# 10_Speed.net
KiCad netlist of a schematic drawn in Altium Designer
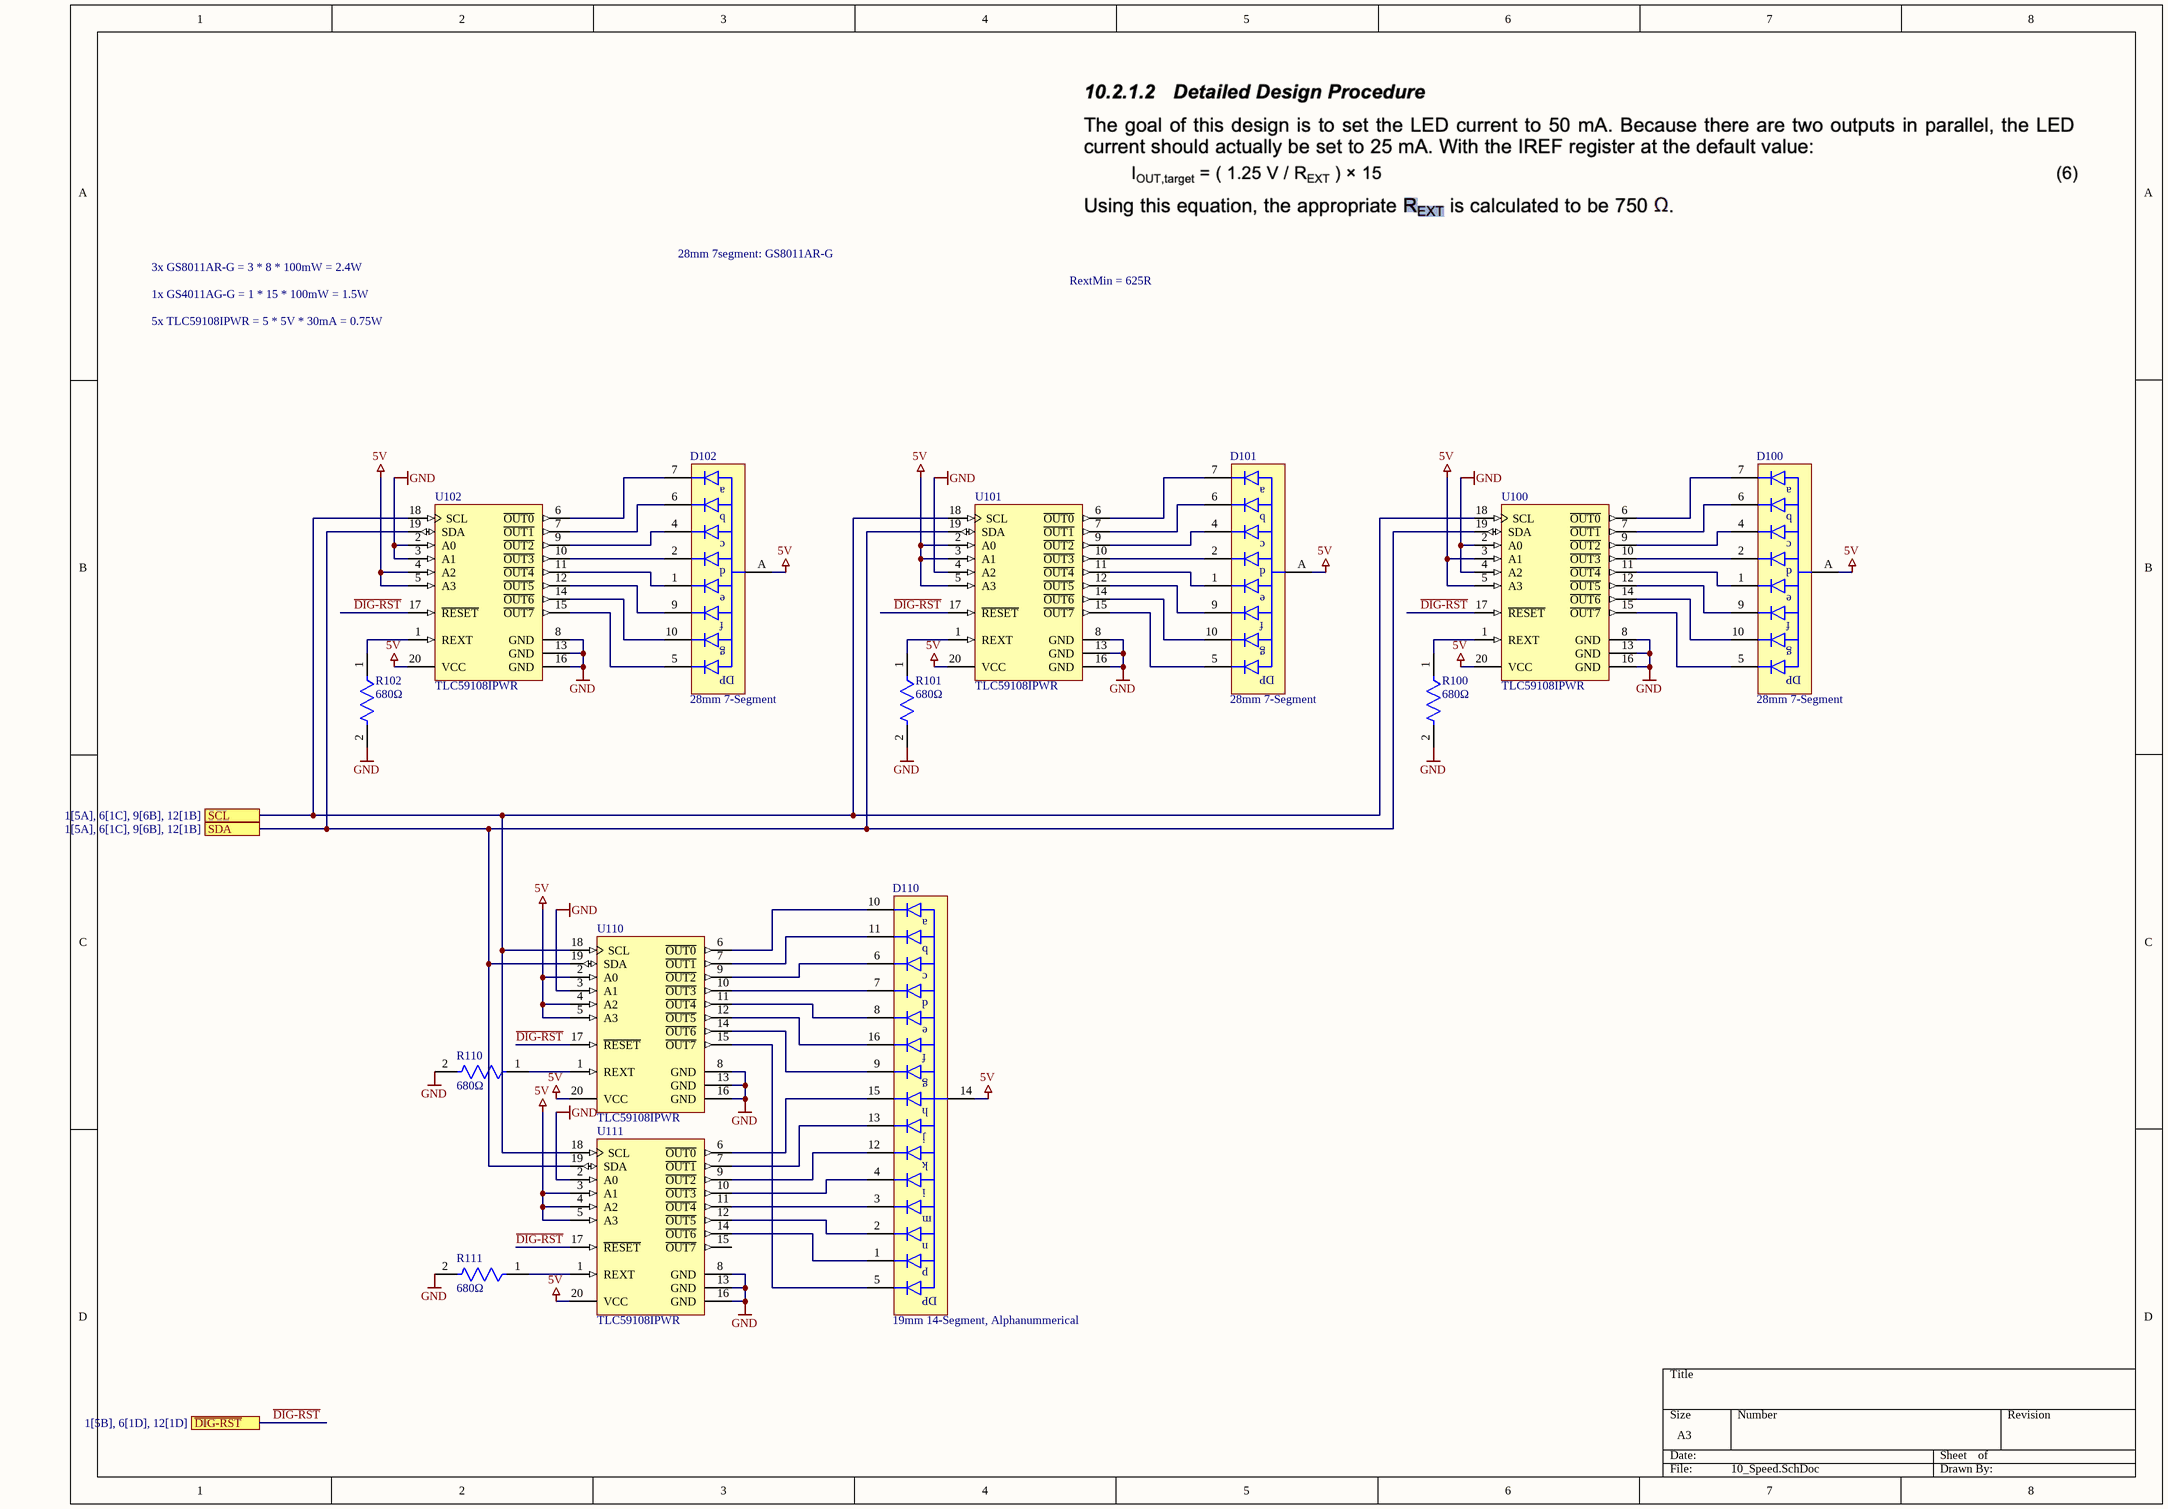
[diagram p0: 10_Speed.SchDoc]

(export (version "E")
  (design (tool "Eeschema 10.0.6"))
  (components
    (comp (ref "D100")
      (value "28mm 7-Segment")
      (footprint "GS8011AR-G")
      (description "SMD, 28x16.8mm 7-Segment")
      (libsource (lib "AltiumLib_MILUTIN") (part "GS8011AR-G"))
    )
    (comp (ref "D101")
      (value "28mm 7-Segment")
      (footprint "GS8011AR-G")
      (description "SMD, 28x16.8mm 7-Segment")
      (libsource (lib "AltiumLib_MILUTIN") (part "GS8011AR-G"))
    )
    (comp (ref "D102")
      (value "28mm 7-Segment")
      (footprint "GS8011AR-G")
      (description "SMD, 28x16.8mm 7-Segment")
      (libsource (lib "AltiumLib_MILUTIN") (part "GS8011AR-G"))
    )
    (comp (ref "D110")
      (value "19mm 14-Segment, Alphanummerical")
      (footprint "GS4011AG-G")
      (description "SMD, 19x9.3mm 14-Segment, Alphanummerical")
      (libsource (lib "AltiumLib_MILUTIN") (part "GS4011AG-G"))
    )
    (comp (ref "R100")
      (value "680Ω")
      (footprint "FP-CRCW0603-e3-IPC_A")
      (description "RES Thick Film, 680Ω, 5%, 0.1W, 200ppm/°C, 0603\r\nCRCW0603680RJNEA")
      (fields (field (name "TOLERANCE") "5%"))
      (libsource (lib "Altium Content Vault") (part "1029c3af85768c4190bb7ad29bc67b5"))
    )
    (comp (ref "R101")
      (value "680Ω")
      (footprint "FP-CRCW0603-e3-IPC_A")
      (description "RES Thick Film, 680Ω, 5%, 0.1W, 200ppm/°C, 0603\r\nCRCW0603680RJNEA")
      (fields (field (name "TOLERANCE") "5%"))
      (libsource (lib "Altium Content Vault") (part "1029c3af85768c4190bb7ad29bc67b5"))
    )
    (comp (ref "R102")
      (value "680Ω")
      (footprint "FP-CRCW0603-e3-IPC_A")
      (description "RES Thick Film, 680Ω, 5%, 0.1W, 200ppm/°C, 0603\r\nCRCW0603680RJNEA")
      (fields (field (name "TOLERANCE") "5%"))
      (libsource (lib "Altium Content Vault") (part "1029c3af85768c4190bb7ad29bc67b5"))
    )
    (comp (ref "R110")
      (value "680Ω")
      (footprint "FP-CRCW0603-e3-IPC_A")
      (description "RES Thick Film, 680Ω, 5%, 0.1W, 200ppm/°C, 0603\r\nCRCW0603680RJNEA")
      (fields (field (name "TOLERANCE") "5%"))
      (libsource (lib "Altium Content Vault") (part "1029c3af85768c4190bb7ad29bc67b5"))
    )
    (comp (ref "R111")
      (value "680Ω")
      (footprint "FP-CRCW0603-e3-IPC_A")
      (description "RES Thick Film, 680Ω, 5%, 0.1W, 200ppm/°C, 0603\r\nCRCW0603680RJNEA")
      (fields (field (name "TOLERANCE") "5%"))
      (libsource (lib "Altium Content Vault") (part "1029c3af85768c4190bb7ad29bc67b5"))
    )
    (comp (ref "U100")
      (value "TLC59108IPWR")
      (footprint "PW0020A_M")
      (fields (field (name "MANUFACTURER") "Texas Instruments"))
      (libsource (lib "Altium Content Vault") (part "TI-TLC59108PW20"))
    )
    (comp (ref "U101")
      (value "TLC59108IPWR")
      (footprint "PW0020A_M")
      (fields (field (name "MANUFACTURER") "Texas Instruments"))
      (libsource (lib "Altium Content Vault") (part "TI-TLC59108PW20"))
    )
    (comp (ref "U102")
      (value "TLC59108IPWR")
      (footprint "PW0020A_M")
      (fields (field (name "MANUFACTURER") "Texas Instruments"))
      (libsource (lib "Altium Content Vault") (part "TI-TLC59108PW20"))
    )
    (comp (ref "U110")
      (value "TLC59108IPWR")
      (footprint "PW0020A_M")
      (fields (field (name "MANUFACTURER") "Texas Instruments"))
      (libsource (lib "Altium Content Vault") (part "TI-TLC59108PW20"))
    )
    (comp (ref "U111")
      (value "TLC59108IPWR")
      (footprint "PW0020A_M")
      (fields (field (name "MANUFACTURER") "Texas Instruments"))
      (libsource (lib "Altium Content Vault") (part "TI-TLC59108PW20"))
    )
  )
  (nets
    (net (code "1") (name "/SCL") (class "Default")
      (node (ref "U100") (pin "18") (pinfunction "SCL_18") (pintype "input"))
      (node (ref "U101") (pin "18") (pinfunction "SCL_18") (pintype "input"))
      (node (ref "U102") (pin "18") (pinfunction "SCL_18") (pintype "input"))
      (node (ref "U110") (pin "18") (pinfunction "SCL_18") (pintype "input"))
      (node (ref "U111") (pin "18") (pinfunction "SCL_18") (pintype "input"))
    )
    (net (code "2") (name "/SDA") (class "Default")
      (node (ref "U100") (pin "19") (pinfunction "SDA_19") (pintype "bidirectional"))
      (node (ref "U101") (pin "19") (pinfunction "SDA_19") (pintype "bidirectional"))
      (node (ref "U102") (pin "19") (pinfunction "SDA_19") (pintype "bidirectional"))
      (node (ref "U110") (pin "19") (pinfunction "SDA_19") (pintype "bidirectional"))
      (node (ref "U111") (pin "19") (pinfunction "SDA_19") (pintype "bidirectional"))
    )
    (net (code "3") (name "/~{DIG-RST}") (class "Default")
      (node (ref "U100") (pin "17") (pinfunction "~{RESET}_17") (pintype "input"))
      (node (ref "U101") (pin "17") (pinfunction "~{RESET}_17") (pintype "input"))
      (node (ref "U102") (pin "17") (pinfunction "~{RESET}_17") (pintype "input"))
      (node (ref "U110") (pin "17") (pinfunction "~{RESET}_17") (pintype "input"))
      (node (ref "U111") (pin "17") (pinfunction "~{RESET}_17") (pintype "input"))
    )
    (net (code "4") (name "5V") (class "Default")
      (node (ref "D100") (pin "A") (pinfunction "A_A") (pintype "passive"))
      (node (ref "D101") (pin "A") (pinfunction "A_A") (pintype "passive"))
      (node (ref "D102") (pin "A") (pinfunction "A_A") (pintype "passive"))
      (node (ref "D110") (pin "14") (pinfunction "14_14") (pintype "passive"))
      (node (ref "U100") (pin "20") (pinfunction "VCC_20") (pintype "power_in"))
      (node (ref "U100") (pin "3") (pinfunction "A1_3") (pintype "input"))
      (node (ref "U100") (pin "5") (pinfunction "A3_5") (pintype "input"))
      (node (ref "U101") (pin "2") (pinfunction "A0_2") (pintype "input"))
      (node (ref "U101") (pin "20") (pinfunction "VCC_20") (pintype "power_in"))
      (node (ref "U101") (pin "3") (pinfunction "A1_3") (pintype "input"))
      (node (ref "U101") (pin "5") (pinfunction "A3_5") (pintype "input"))
      (node (ref "U102") (pin "20") (pinfunction "VCC_20") (pintype "power_in"))
      (node (ref "U102") (pin "4") (pinfunction "A2_4") (pintype "input"))
      (node (ref "U102") (pin "5") (pinfunction "A3_5") (pintype "input"))
      (node (ref "U110") (pin "2") (pinfunction "A0_2") (pintype "input"))
      (node (ref "U110") (pin "20") (pinfunction "VCC_20") (pintype "power_in"))
      (node (ref "U110") (pin "4") (pinfunction "A2_4") (pintype "input"))
      (node (ref "U110") (pin "5") (pinfunction "A3_5") (pintype "input"))
      (node (ref "U111") (pin "20") (pinfunction "VCC_20") (pintype "power_in"))
      (node (ref "U111") (pin "3") (pinfunction "A1_3") (pintype "input"))
      (node (ref "U111") (pin "4") (pinfunction "A2_4") (pintype "input"))
      (node (ref "U111") (pin "5") (pinfunction "A3_5") (pintype "input"))
    )
    (net (code "5") (name "GND") (class "Default")
      (node (ref "R100") (pin "2") (pinfunction "2_2") (pintype "passive"))
      (node (ref "R101") (pin "2") (pinfunction "2_2") (pintype "passive"))
      (node (ref "R102") (pin "2") (pinfunction "2_2") (pintype "passive"))
      (node (ref "R110") (pin "2") (pinfunction "2_2") (pintype "passive"))
      (node (ref "R111") (pin "2") (pinfunction "2_2") (pintype "passive"))
      (node (ref "U100") (pin "13") (pinfunction "GND_13") (pintype "power_in"))
      (node (ref "U100") (pin "16") (pinfunction "GND_16") (pintype "power_in"))
      (node (ref "U100") (pin "2") (pinfunction "A0_2") (pintype "input"))
      (node (ref "U100") (pin "4") (pinfunction "A2_4") (pintype "input"))
      (node (ref "U100") (pin "8") (pinfunction "GND_8") (pintype "power_in"))
      (node (ref "U101") (pin "13") (pinfunction "GND_13") (pintype "power_in"))
      (node (ref "U101") (pin "16") (pinfunction "GND_16") (pintype "power_in"))
      (node (ref "U101") (pin "4") (pinfunction "A2_4") (pintype "input"))
      (node (ref "U101") (pin "8") (pinfunction "GND_8") (pintype "power_in"))
      (node (ref "U102") (pin "13") (pinfunction "GND_13") (pintype "power_in"))
      (node (ref "U102") (pin "16") (pinfunction "GND_16") (pintype "power_in"))
      (node (ref "U102") (pin "2") (pinfunction "A0_2") (pintype "input"))
      (node (ref "U102") (pin "3") (pinfunction "A1_3") (pintype "input"))
      (node (ref "U102") (pin "8") (pinfunction "GND_8") (pintype "power_in"))
      (node (ref "U110") (pin "13") (pinfunction "GND_13") (pintype "power_in"))
      (node (ref "U110") (pin "16") (pinfunction "GND_16") (pintype "power_in"))
      (node (ref "U110") (pin "3") (pinfunction "A1_3") (pintype "input"))
      (node (ref "U110") (pin "8") (pinfunction "GND_8") (pintype "power_in"))
      (node (ref "U111") (pin "13") (pinfunction "GND_13") (pintype "power_in"))
      (node (ref "U111") (pin "16") (pinfunction "GND_16") (pintype "power_in"))
      (node (ref "U111") (pin "2") (pinfunction "A0_2") (pintype "input"))
      (node (ref "U111") (pin "8") (pinfunction "GND_8") (pintype "power_in"))
    )
    (net (code "6") (name "Net-(U100-REXT)") (class "Default")
      (node (ref "R100") (pin "1") (pinfunction "1_1") (pintype "passive"))
      (node (ref "U100") (pin "1") (pinfunction "REXT_1") (pintype "input"))
    )
    (net (code "7") (name "Net-(U100-~{OUT0})") (class "Default")
      (node (ref "D100") (pin "7") (pinfunction "7_7") (pintype "passive"))
      (node (ref "U100") (pin "6") (pinfunction "~{OUT0}_6") (pintype "output"))
    )
    (net (code "8") (name "Net-(U100-~{OUT1})") (class "Default")
      (node (ref "D100") (pin "6") (pinfunction "6_6") (pintype "passive"))
      (node (ref "U100") (pin "7") (pinfunction "~{OUT1}_7") (pintype "output"))
    )
    (net (code "9") (name "Net-(U100-~{OUT2})") (class "Default")
      (node (ref "D100") (pin "4") (pinfunction "4_4") (pintype "passive"))
      (node (ref "U100") (pin "9") (pinfunction "~{OUT2}_9") (pintype "output"))
    )
    (net (code "10") (name "Net-(U100-~{OUT3})") (class "Default")
      (node (ref "D100") (pin "2") (pinfunction "2_2") (pintype "passive"))
      (node (ref "U100") (pin "10") (pinfunction "~{OUT3}_10") (pintype "output"))
    )
    (net (code "11") (name "Net-(U100-~{OUT4})") (class "Default")
      (node (ref "D100") (pin "1") (pinfunction "1_1") (pintype "passive"))
      (node (ref "U100") (pin "11") (pinfunction "~{OUT4}_11") (pintype "output"))
    )
    (net (code "12") (name "Net-(U100-~{OUT5})") (class "Default")
      (node (ref "D100") (pin "9") (pinfunction "9_9") (pintype "passive"))
      (node (ref "U100") (pin "12") (pinfunction "~{OUT5}_12") (pintype "output"))
    )
    (net (code "13") (name "Net-(U100-~{OUT6})") (class "Default")
      (node (ref "D100") (pin "10") (pinfunction "10_10") (pintype "passive"))
      (node (ref "U100") (pin "14") (pinfunction "~{OUT6}_14") (pintype "output"))
    )
    (net (code "14") (name "Net-(U100-~{OUT7})") (class "Default")
      (node (ref "D100") (pin "5") (pinfunction "5_5") (pintype "passive"))
      (node (ref "U100") (pin "15") (pinfunction "~{OUT7}_15") (pintype "output"))
    )
    (net (code "15") (name "Net-(U101-REXT)") (class "Default")
      (node (ref "R101") (pin "1") (pinfunction "1_1") (pintype "passive"))
      (node (ref "U101") (pin "1") (pinfunction "REXT_1") (pintype "input"))
    )
    (net (code "16") (name "Net-(U101-~{OUT0})") (class "Default")
      (node (ref "D101") (pin "7") (pinfunction "7_7") (pintype "passive"))
      (node (ref "U101") (pin "6") (pinfunction "~{OUT0}_6") (pintype "output"))
    )
    (net (code "17") (name "Net-(U101-~{OUT1})") (class "Default")
      (node (ref "D101") (pin "6") (pinfunction "6_6") (pintype "passive"))
      (node (ref "U101") (pin "7") (pinfunction "~{OUT1}_7") (pintype "output"))
    )
    (net (code "18") (name "Net-(U101-~{OUT2})") (class "Default")
      (node (ref "D101") (pin "4") (pinfunction "4_4") (pintype "passive"))
      (node (ref "U101") (pin "9") (pinfunction "~{OUT2}_9") (pintype "output"))
    )
    (net (code "19") (name "Net-(U101-~{OUT3})") (class "Default")
      (node (ref "D101") (pin "2") (pinfunction "2_2") (pintype "passive"))
      (node (ref "U101") (pin "10") (pinfunction "~{OUT3}_10") (pintype "output"))
    )
    (net (code "20") (name "Net-(U101-~{OUT4})") (class "Default")
      (node (ref "D101") (pin "1") (pinfunction "1_1") (pintype "passive"))
      (node (ref "U101") (pin "11") (pinfunction "~{OUT4}_11") (pintype "output"))
    )
    (net (code "21") (name "Net-(U101-~{OUT5})") (class "Default")
      (node (ref "D101") (pin "9") (pinfunction "9_9") (pintype "passive"))
      (node (ref "U101") (pin "12") (pinfunction "~{OUT5}_12") (pintype "output"))
    )
    (net (code "22") (name "Net-(U101-~{OUT6})") (class "Default")
      (node (ref "D101") (pin "10") (pinfunction "10_10") (pintype "passive"))
      (node (ref "U101") (pin "14") (pinfunction "~{OUT6}_14") (pintype "output"))
    )
    (net (code "23") (name "Net-(U101-~{OUT7})") (class "Default")
      (node (ref "D101") (pin "5") (pinfunction "5_5") (pintype "passive"))
      (node (ref "U101") (pin "15") (pinfunction "~{OUT7}_15") (pintype "output"))
    )
    (net (code "24") (name "Net-(U102-REXT)") (class "Default")
      (node (ref "R102") (pin "1") (pinfunction "1_1") (pintype "passive"))
      (node (ref "U102") (pin "1") (pinfunction "REXT_1") (pintype "input"))
    )
    (net (code "25") (name "Net-(U102-~{OUT0})") (class "Default")
      (node (ref "D102") (pin "7") (pinfunction "7_7") (pintype "passive"))
      (node (ref "U102") (pin "6") (pinfunction "~{OUT0}_6") (pintype "output"))
    )
    (net (code "26") (name "Net-(U102-~{OUT1})") (class "Default")
      (node (ref "D102") (pin "6") (pinfunction "6_6") (pintype "passive"))
      (node (ref "U102") (pin "7") (pinfunction "~{OUT1}_7") (pintype "output"))
    )
    (net (code "27") (name "Net-(U102-~{OUT2})") (class "Default")
      (node (ref "D102") (pin "4") (pinfunction "4_4") (pintype "passive"))
      (node (ref "U102") (pin "9") (pinfunction "~{OUT2}_9") (pintype "output"))
    )
    (net (code "28") (name "Net-(U102-~{OUT3})") (class "Default")
      (node (ref "D102") (pin "2") (pinfunction "2_2") (pintype "passive"))
      (node (ref "U102") (pin "10") (pinfunction "~{OUT3}_10") (pintype "output"))
    )
    (net (code "29") (name "Net-(U102-~{OUT4})") (class "Default")
      (node (ref "D102") (pin "1") (pinfunction "1_1") (pintype "passive"))
      (node (ref "U102") (pin "11") (pinfunction "~{OUT4}_11") (pintype "output"))
    )
    (net (code "30") (name "Net-(U102-~{OUT5})") (class "Default")
      (node (ref "D102") (pin "9") (pinfunction "9_9") (pintype "passive"))
      (node (ref "U102") (pin "12") (pinfunction "~{OUT5}_12") (pintype "output"))
    )
    (net (code "31") (name "Net-(U102-~{OUT6})") (class "Default")
      (node (ref "D102") (pin "10") (pinfunction "10_10") (pintype "passive"))
      (node (ref "U102") (pin "14") (pinfunction "~{OUT6}_14") (pintype "output"))
    )
    (net (code "32") (name "Net-(U102-~{OUT7})") (class "Default")
      (node (ref "D102") (pin "5") (pinfunction "5_5") (pintype "passive"))
      (node (ref "U102") (pin "15") (pinfunction "~{OUT7}_15") (pintype "output"))
    )
    (net (code "33") (name "Net-(U110-REXT)") (class "Default")
      (node (ref "R110") (pin "1") (pinfunction "1_1") (pintype "passive"))
      (node (ref "U110") (pin "1") (pinfunction "REXT_1") (pintype "input"))
    )
    (net (code "34") (name "Net-(U110-~{OUT0})") (class "Default")
      (node (ref "D110") (pin "10") (pinfunction "10_10") (pintype "passive"))
      (node (ref "U110") (pin "6") (pinfunction "~{OUT0}_6") (pintype "output"))
    )
    (net (code "35") (name "Net-(U110-~{OUT1})") (class "Default")
      (node (ref "D110") (pin "11") (pinfunction "11_11") (pintype "passive"))
      (node (ref "U110") (pin "7") (pinfunction "~{OUT1}_7") (pintype "output"))
    )
    (net (code "36") (name "Net-(U110-~{OUT2})") (class "Default")
      (node (ref "D110") (pin "6") (pinfunction "6_6") (pintype "passive"))
      (node (ref "U110") (pin "9") (pinfunction "~{OUT2}_9") (pintype "output"))
    )
    (net (code "37") (name "Net-(U110-~{OUT3})") (class "Default")
      (node (ref "D110") (pin "7") (pinfunction "7_7") (pintype "passive"))
      (node (ref "U110") (pin "10") (pinfunction "~{OUT3}_10") (pintype "output"))
    )
    (net (code "38") (name "Net-(U110-~{OUT4})") (class "Default")
      (node (ref "D110") (pin "8") (pinfunction "8_8") (pintype "passive"))
      (node (ref "U110") (pin "11") (pinfunction "~{OUT4}_11") (pintype "output"))
    )
    (net (code "39") (name "Net-(U110-~{OUT5})") (class "Default")
      (node (ref "D110") (pin "16") (pinfunction "16_16") (pintype "passive"))
      (node (ref "U110") (pin "12") (pinfunction "~{OUT5}_12") (pintype "output"))
    )
    (net (code "40") (name "Net-(U110-~{OUT6})") (class "Default")
      (node (ref "D110") (pin "9") (pinfunction "9_9") (pintype "passive"))
      (node (ref "U110") (pin "14") (pinfunction "~{OUT6}_14") (pintype "output"))
    )
    (net (code "41") (name "Net-(U110-~{OUT7})") (class "Default")
      (node (ref "D110") (pin "5") (pinfunction "5_5") (pintype "passive"))
      (node (ref "U110") (pin "15") (pinfunction "~{OUT7}_15") (pintype "output"))
    )
    (net (code "42") (name "Net-(U111-REXT)") (class "Default")
      (node (ref "R111") (pin "1") (pinfunction "1_1") (pintype "passive"))
      (node (ref "U111") (pin "1") (pinfunction "REXT_1") (pintype "input"))
    )
    (net (code "43") (name "Net-(U111-~{OUT0})") (class "Default")
      (node (ref "D110") (pin "15") (pinfunction "15_15") (pintype "passive"))
      (node (ref "U111") (pin "6") (pinfunction "~{OUT0}_6") (pintype "output"))
    )
    (net (code "44") (name "Net-(U111-~{OUT1})") (class "Default")
      (node (ref "D110") (pin "13") (pinfunction "13_13") (pintype "passive"))
      (node (ref "U111") (pin "7") (pinfunction "~{OUT1}_7") (pintype "output"))
    )
    (net (code "45") (name "Net-(U111-~{OUT2})") (class "Default")
      (node (ref "D110") (pin "12") (pinfunction "12_12") (pintype "passive"))
      (node (ref "U111") (pin "9") (pinfunction "~{OUT2}_9") (pintype "output"))
    )
    (net (code "46") (name "Net-(U111-~{OUT3})") (class "Default")
      (node (ref "D110") (pin "4") (pinfunction "4_4") (pintype "passive"))
      (node (ref "U111") (pin "10") (pinfunction "~{OUT3}_10") (pintype "output"))
    )
    (net (code "47") (name "Net-(U111-~{OUT4})") (class "Default")
      (node (ref "D110") (pin "3") (pinfunction "3_3") (pintype "passive"))
      (node (ref "U111") (pin "11") (pinfunction "~{OUT4}_11") (pintype "output"))
    )
    (net (code "48") (name "Net-(U111-~{OUT5})") (class "Default")
      (node (ref "D110") (pin "2") (pinfunction "2_2") (pintype "passive"))
      (node (ref "U111") (pin "12") (pinfunction "~{OUT5}_12") (pintype "output"))
    )
    (net (code "49") (name "Net-(U111-~{OUT6})") (class "Default")
      (node (ref "D110") (pin "1") (pinfunction "1_1") (pintype "passive"))
      (node (ref "U111") (pin "14") (pinfunction "~{OUT6}_14") (pintype "output"))
    )
    (net (code "50") (name "unconnected-(U111-~{OUT7}-Pad15)") (class "Default")
      (node (ref "U111") (pin "15") (pinfunction "~{OUT7}_15") (pintype "output"))
    )
  )
)
